# 1-Schematic_ISMWAVER433_MODULE.net
KiCad netlist of a schematic drawn in EasyEDA
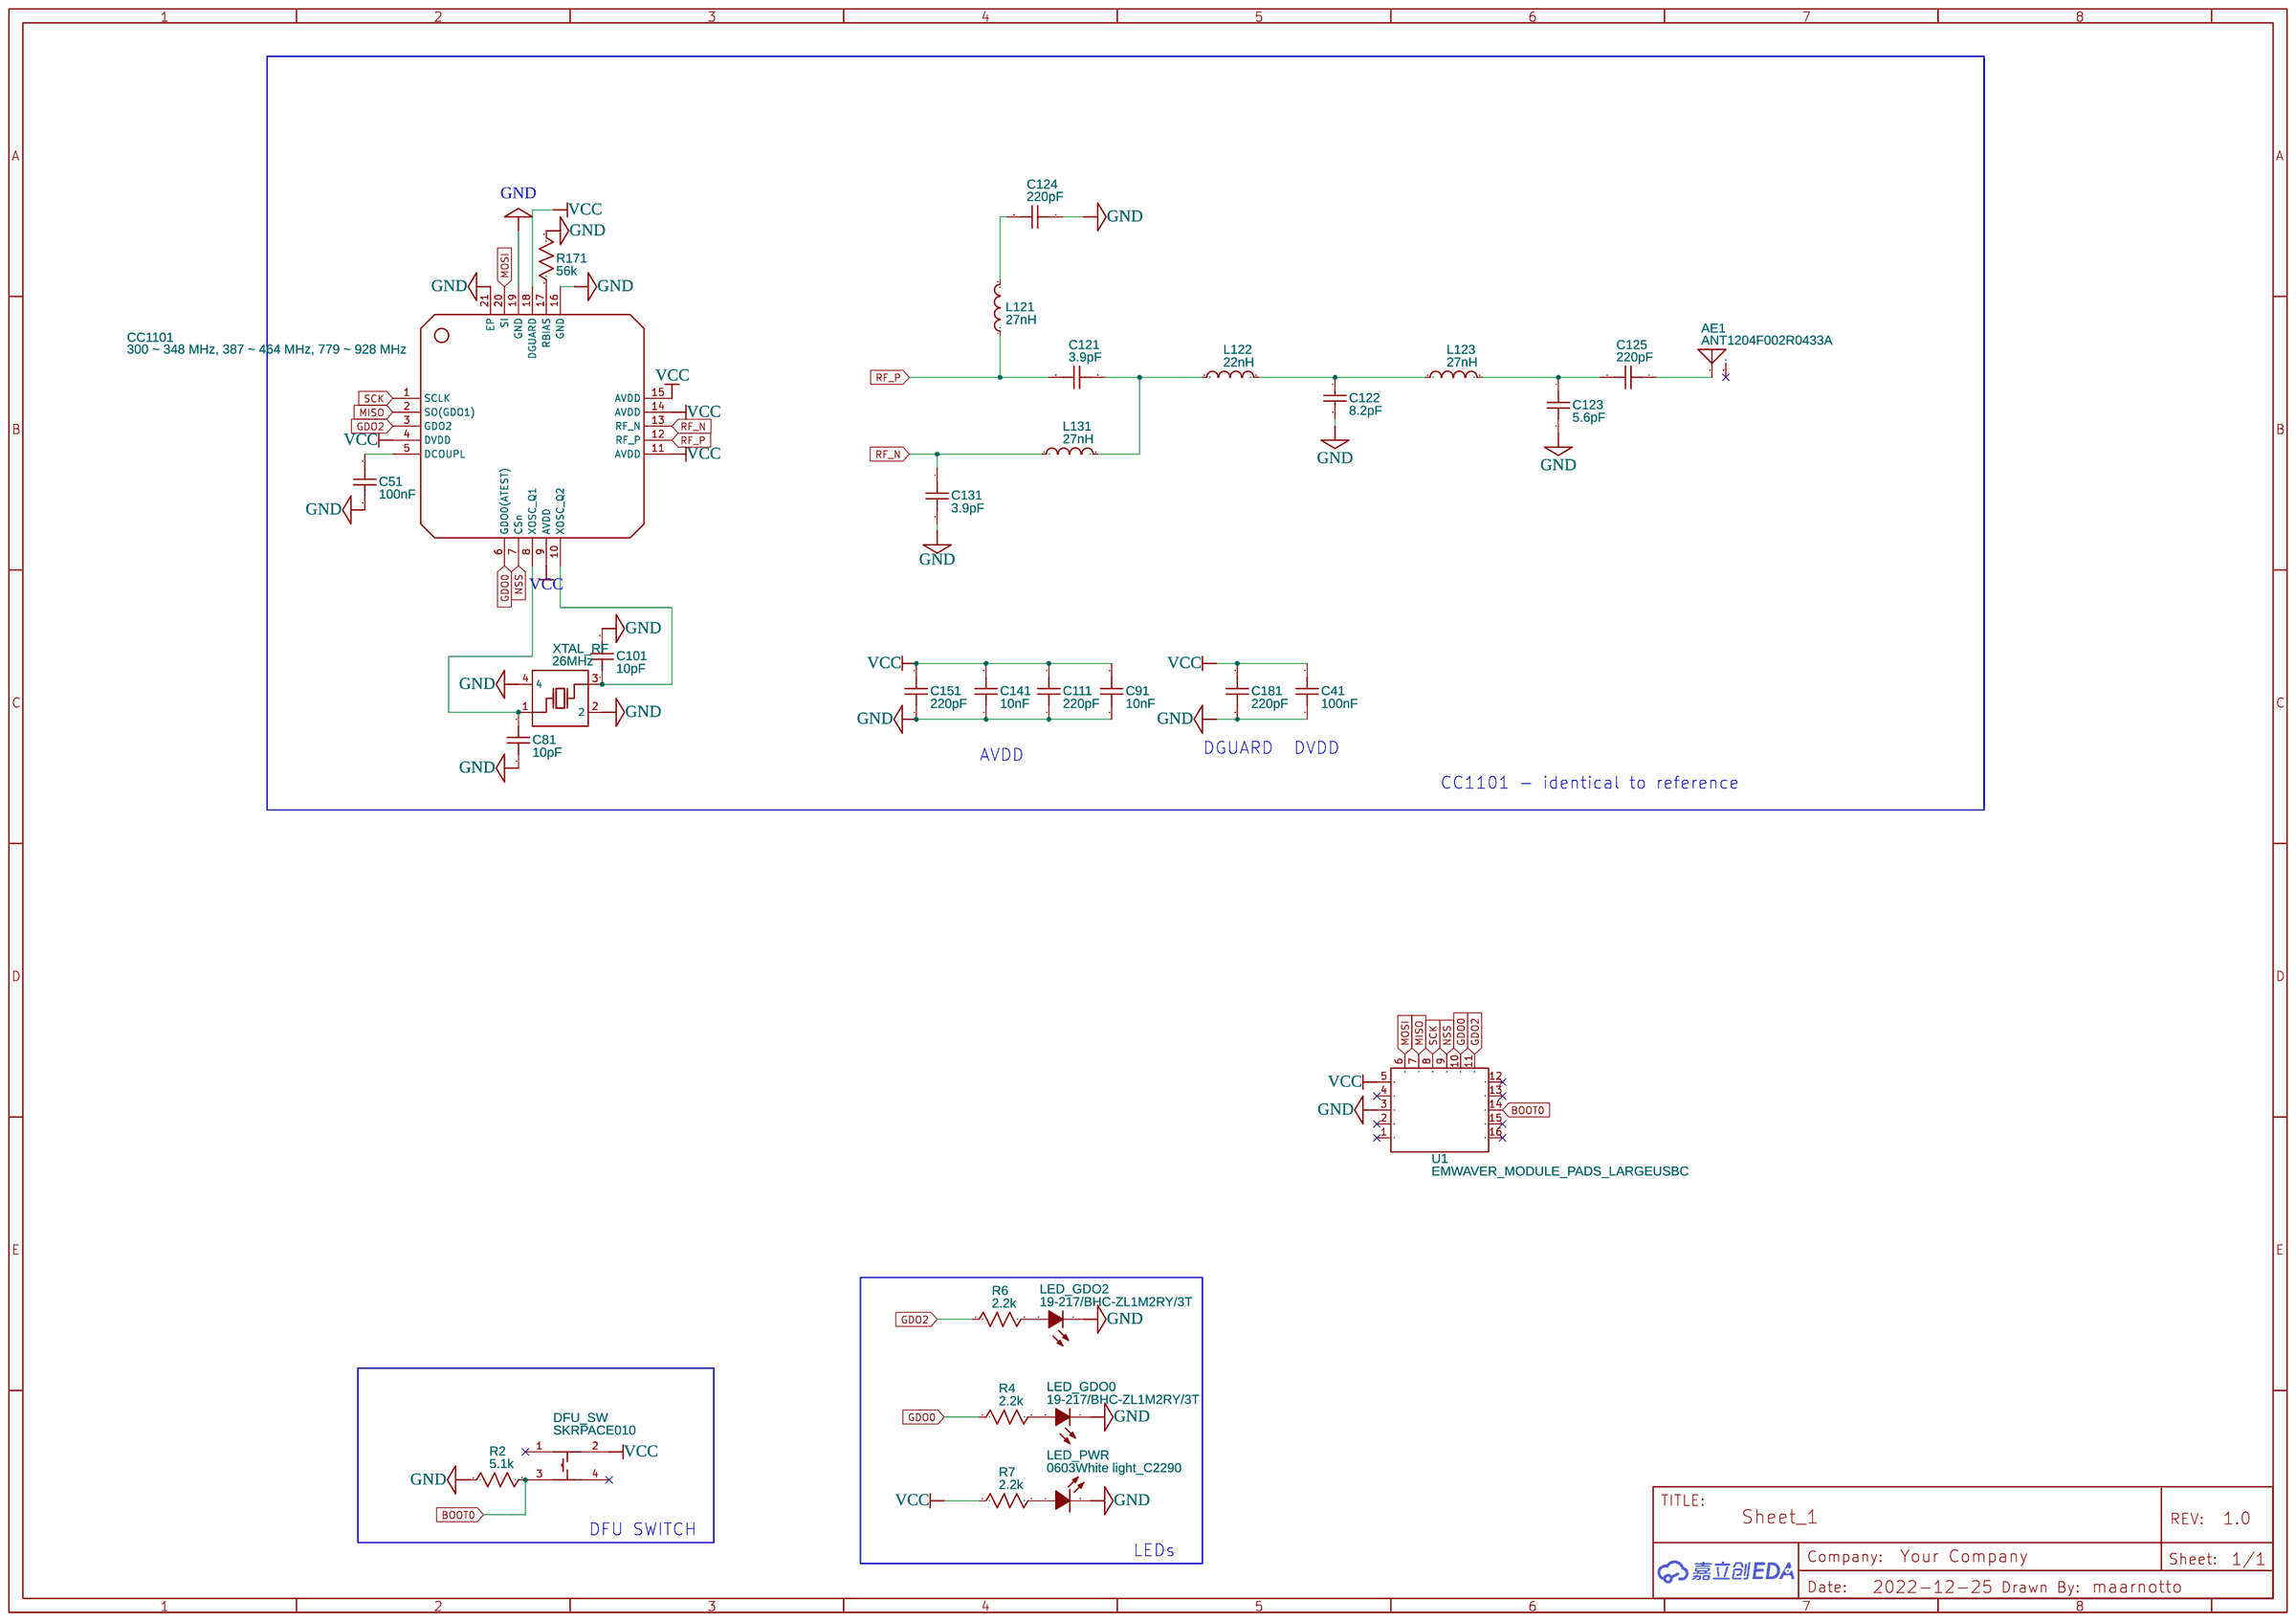
[diagram p0: schematic sheet]

(export (version "E")
  (design (tool "Eeschema 10.0.6"))
  (components
    (comp (ref "AE1")
      (value "ANT1204F002R0433A")
      (fields (field (name "Manufacturer") "YAGEO(国巨)"))
      (libsource (lib "") (part "ANT1204F002R0433A"))
    )
    (comp (ref "C41") (value "100nF") (libsource (lib "") (part "C_0402_US")))
    (comp (ref "C51") (value "100nF") (libsource (lib "") (part "C_0402_US")))
    (comp (ref "C81") (value "10pF") (libsource (lib "") (part "C_0402_US")))
    (comp (ref "C91") (value "10nF") (libsource (lib "") (part "C_0402_US")))
    (comp (ref "C101") (value "10pF") (libsource (lib "") (part "C_0402_US_2")))
    (comp (ref "C111") (value "220pF") (libsource (lib "") (part "C_0402_US")))
    (comp (ref "C121") (value "3.9pF") (libsource (lib "") (part "C_0402_US_1")))
    (comp (ref "C122")
      (value "8.2pF")
      (fields (field (name "Manufacturer Part") "0402CG8R2C500NT") (field (name "Manufacturer") "FH(风华)"))
      (libsource (lib "") (part "0402CG8R2C500NT"))
    )
    (comp (ref "C123") (value "5.6pF") (libsource (lib "") (part "C_0402_US")))
    (comp (ref "C124") (value "220pF") (libsource (lib "") (part "C_0402_US_1")))
    (comp (ref "C125") (value "220pF") (libsource (lib "") (part "C_0402_US_1")))
    (comp (ref "C131") (value "3.9pF") (libsource (lib "") (part "C_0402_US")))
    (comp (ref "C141") (value "10nF") (libsource (lib "") (part "C_0402_US")))
    (comp (ref "C151") (value "220pF") (libsource (lib "") (part "C_0402_US")))
    (comp (ref "C181") (value "220pF") (libsource (lib "") (part "C_0402_US")))
    (comp (ref "CC1101")
      (value "300 ~ 348 MHz, 387 ~ 464 MHz, 779 ~ 928 MHz")
      (fields (field (name "Manufacturer Part") "CC1101RGPR") (field (name "Manufacturer") "TI(德州仪器)"))
      (libsource (lib "") (part "CC1101RGPR"))
    )
    (comp (ref "DFU_SW")
      (value "SKRPACE010")
      (fields (field (name "Manufacturer") "ALPSALPINE(阿尔卑斯阿尔派)"))
      (libsource (lib "") (part "SKRPACE010"))
    )
    (comp (ref "L121") (value "27nH") (libsource (lib "") (part "L0402_US_1")))
    (comp (ref "L122") (value "22nH") (libsource (lib "") (part "L0402_US")))
    (comp (ref "L123") (value "27nH") (libsource (lib "") (part "L0402_US_2")))
    (comp (ref "L131") (value "27nH") (libsource (lib "") (part "L0402_US")))
    (comp (ref "LED_GDO0")
      (value "19-217/BHC-ZL1M2RY/3T")
      (fields (field (name "Manufacturer") "EVERLIGHT(亿光)"))
      (libsource (lib "") (part "19-217/BHC-ZL1M2RY/3T"))
    )
    (comp (ref "LED_GDO2")
      (value "19-217/BHC-ZL1M2RY/3T")
      (fields (field (name "Manufacturer") "EVERLIGHT(亿光)"))
      (libsource (lib "") (part "19-217/BHC-ZL1M2RY/3T"))
    )
    (comp (ref "LED_PWR")
      (value "0603White light_C2290")
      (fields (field (name "Manufacturer Part") "KT-0603白灯"))
      (libsource (lib "") (part "0603White light_C2290"))
    )
    (comp (ref "R2") (value "5.1k") (libsource (lib "") (part "R_0603_US")))
    (comp (ref "R4") (value "2.2k") (libsource (lib "") (part "R_0603_US")))
    (comp (ref "R6") (value "2.2k") (libsource (lib "") (part "R_0603_US")))
    (comp (ref "R7") (value "2.2k") (libsource (lib "") (part "R_0603_US")))
    (comp (ref "R171") (value "56k") (libsource (lib "") (part "R_0402_US")))
    (comp (ref "U1")
      (value "EMWAVER_MODULE_PADS_LARGEUSBC")
      (libsource (lib "") (part "EMWAVER_MODULE_PADS_LARGEUSBC"))
    )
    (comp (ref "XTAL_RF")
      (value "26MHz")
      (fields (field (name "Manufacturer Part") "3S26000333") (field (name "Manufacturer") "YL(惠伦晶体)"))
      (libsource (lib "") (part "3S26000333"))
    )
  )
  (nets
    (net (code "1") (name "BOOT0") (class "Default")
      (node (ref "DFU_SW") (pin "3") (pinfunction "3_3") (pintype "unspecified"))
      (node (ref "R2") (pin "2") (pinfunction "2_2") (pintype "unspecified"))
      (node (ref "U1") (pin "14") (pinfunction "14_14") (pintype "unspecified"))
    )
    (net (code "2") (name "GDO0") (class "Default")
      (node (ref "CC1101") (pin "6") (pinfunction "GDO0(ATEST)_6") (pintype "unspecified"))
      (node (ref "R4") (pin "1") (pinfunction "1_1") (pintype "unspecified"))
      (node (ref "U1") (pin "10") (pinfunction "10_10") (pintype "unspecified"))
    )
    (net (code "3") (name "GDO2") (class "Default")
      (node (ref "CC1101") (pin "3") (pinfunction "GDO2_3") (pintype "unspecified"))
      (node (ref "R6") (pin "1") (pinfunction "1_1") (pintype "unspecified"))
      (node (ref "U1") (pin "11") (pinfunction "11_11") (pintype "unspecified"))
    )
    (net (code "4") (name "GND") (class "Default")
      (node (ref "C101") (pin "2") (pinfunction "2_2") (pintype "unspecified"))
      (node (ref "C111") (pin "2") (pinfunction "2_2") (pintype "unspecified"))
      (node (ref "C122") (pin "1") (pinfunction "1_1") (pintype "input"))
      (node (ref "C123") (pin "2") (pinfunction "2_2") (pintype "unspecified"))
      (node (ref "C124") (pin "1") (pinfunction "1_1") (pintype "unspecified"))
      (node (ref "C131") (pin "2") (pinfunction "2_2") (pintype "unspecified"))
      (node (ref "C141") (pin "2") (pinfunction "2_2") (pintype "unspecified"))
      (node (ref "C151") (pin "2") (pinfunction "2_2") (pintype "unspecified"))
      (node (ref "C181") (pin "2") (pinfunction "2_2") (pintype "unspecified"))
      (node (ref "C41") (pin "2") (pinfunction "2_2") (pintype "unspecified"))
      (node (ref "C51") (pin "2") (pinfunction "2_2") (pintype "unspecified"))
      (node (ref "C81") (pin "2") (pinfunction "2_2") (pintype "unspecified"))
      (node (ref "C91") (pin "2") (pinfunction "2_2") (pintype "unspecified"))
      (node (ref "CC1101") (pin "16") (pinfunction "GND_16") (pintype "unspecified"))
      (node (ref "CC1101") (pin "19") (pinfunction "GND_19") (pintype "unspecified"))
      (node (ref "CC1101") (pin "21") (pinfunction "EP_21") (pintype "unspecified"))
      (node (ref "LED_GDO0") (pin "1") (pinfunction "C_1") (pintype "input"))
      (node (ref "LED_GDO2") (pin "1") (pinfunction "C_1") (pintype "input"))
      (node (ref "LED_PWR") (pin "2") (pinfunction "K_2") (pintype "unspecified"))
      (node (ref "R171") (pin "2") (pinfunction "2_2") (pintype "unspecified"))
      (node (ref "R2") (pin "1") (pinfunction "1_1") (pintype "unspecified"))
      (node (ref "U1") (pin "3") (pinfunction "3_3") (pintype "unspecified"))
      (node (ref "XTAL_RF") (pin "2") (pinfunction "2_2") (pintype "unspecified"))
      (node (ref "XTAL_RF") (pin "4") (pinfunction "4_4") (pintype "unspecified"))
    )
    (net (code "5") (name "MISO") (class "Default")
      (node (ref "CC1101") (pin "2") (pinfunction "SO(GDO1)_2") (pintype "unspecified"))
      (node (ref "U1") (pin "7") (pinfunction "7_7") (pintype "unspecified"))
    )
    (net (code "6") (name "MOSI") (class "Default")
      (node (ref "CC1101") (pin "20") (pinfunction "SI_20") (pintype "unspecified"))
      (node (ref "U1") (pin "6") (pinfunction "6_6") (pintype "unspecified"))
    )
    (net (code "7") (name "NSS") (class "Default")
      (node (ref "CC1101") (pin "7") (pinfunction "CSn_7") (pintype "unspecified"))
      (node (ref "U1") (pin "9") (pinfunction "9_9") (pintype "unspecified"))
    )
    (net (code "8") (name "Net-(AE1-PadS1)") (class "Default")
      (node (ref "AE1") (pin "S1") (pinfunction "S1_S1") (pintype "unspecified"))
      (node (ref "C125") (pin "1") (pinfunction "1_1") (pintype "unspecified"))
    )
    (net (code "9") (name "Net-(C121-Pad1)") (class "Default")
      (node (ref "C121") (pin "1") (pinfunction "1_1") (pintype "unspecified"))
      (node (ref "L122") (pin "1") (pinfunction "1_1") (pintype "unspecified"))
      (node (ref "L131") (pin "2") (pinfunction "2_2") (pintype "unspecified"))
    )
    (net (code "10") (name "Net-(C122-Pad2)") (class "Default")
      (node (ref "C122") (pin "2") (pinfunction "2_2") (pintype "input"))
      (node (ref "L122") (pin "2") (pinfunction "2_2") (pintype "unspecified"))
      (node (ref "L123") (pin "1") (pinfunction "1_1") (pintype "unspecified"))
    )
    (net (code "11") (name "Net-(C123-Pad1)") (class "Default")
      (node (ref "C123") (pin "1") (pinfunction "1_1") (pintype "unspecified"))
      (node (ref "C125") (pin "2") (pinfunction "2_2") (pintype "unspecified"))
      (node (ref "L123") (pin "2") (pinfunction "2_2") (pintype "unspecified"))
    )
    (net (code "12") (name "Net-(C124-Pad2)") (class "Default")
      (node (ref "C124") (pin "2") (pinfunction "2_2") (pintype "unspecified"))
      (node (ref "L121") (pin "2") (pinfunction "2_2") (pintype "unspecified"))
    )
    (net (code "13") (name "Net-(CC1101-DCOUPL)") (class "Default")
      (node (ref "C51") (pin "1") (pinfunction "1_1") (pintype "unspecified"))
      (node (ref "CC1101") (pin "5") (pinfunction "DCOUPL_5") (pintype "unspecified"))
    )
    (net (code "14") (name "Net-(CC1101-RBIAS)") (class "Default")
      (node (ref "CC1101") (pin "17") (pinfunction "RBIAS_17") (pintype "unspecified"))
      (node (ref "R171") (pin "1") (pinfunction "1_1") (pintype "unspecified"))
    )
    (net (code "15") (name "Net-(CC1101-XOSC_Q1)") (class "Default")
      (node (ref "C81") (pin "1") (pinfunction "1_1") (pintype "unspecified"))
      (node (ref "CC1101") (pin "8") (pinfunction "XOSC_Q1_8") (pintype "unspecified"))
      (node (ref "XTAL_RF") (pin "1") (pinfunction "OSC1_1") (pintype "unspecified"))
    )
    (net (code "16") (name "Net-(CC1101-XOSC_Q2)") (class "Default")
      (node (ref "C101") (pin "1") (pinfunction "1_1") (pintype "unspecified"))
      (node (ref "CC1101") (pin "10") (pinfunction "XOSC_Q2_10") (pintype "unspecified"))
      (node (ref "XTAL_RF") (pin "3") (pinfunction "OSC2_3") (pintype "unspecified"))
    )
    (net (code "17") (name "Net-(LED_GDO0-A)") (class "Default")
      (node (ref "LED_GDO0") (pin "2") (pinfunction "A_2") (pintype "input"))
      (node (ref "R4") (pin "2") (pinfunction "2_2") (pintype "unspecified"))
    )
    (net (code "18") (name "Net-(LED_GDO2-A)") (class "Default")
      (node (ref "LED_GDO2") (pin "2") (pinfunction "A_2") (pintype "input"))
      (node (ref "R6") (pin "2") (pinfunction "2_2") (pintype "unspecified"))
    )
    (net (code "19") (name "Net-(LED_PWR-A)") (class "Default")
      (node (ref "LED_PWR") (pin "1") (pinfunction "A_1") (pintype "unspecified"))
      (node (ref "R7") (pin "2") (pinfunction "2_2") (pintype "unspecified"))
    )
    (net (code "20") (name "RF_N") (class "Default")
      (node (ref "C131") (pin "1") (pinfunction "1_1") (pintype "unspecified"))
      (node (ref "CC1101") (pin "13") (pinfunction "RF_N_13") (pintype "unspecified"))
      (node (ref "L131") (pin "1") (pinfunction "1_1") (pintype "unspecified"))
    )
    (net (code "21") (name "RF_P") (class "Default")
      (node (ref "C121") (pin "2") (pinfunction "2_2") (pintype "unspecified"))
      (node (ref "CC1101") (pin "12") (pinfunction "RF_P_12") (pintype "unspecified"))
      (node (ref "L121") (pin "1") (pinfunction "1_1") (pintype "unspecified"))
    )
    (net (code "22") (name "SCK") (class "Default")
      (node (ref "CC1101") (pin "1") (pinfunction "SCLK_1") (pintype "unspecified"))
      (node (ref "U1") (pin "8") (pinfunction "8_8") (pintype "unspecified"))
    )
    (net (code "23") (name "VCC") (class "Default")
      (node (ref "C111") (pin "1") (pinfunction "1_1") (pintype "unspecified"))
      (node (ref "C141") (pin "1") (pinfunction "1_1") (pintype "unspecified"))
      (node (ref "C151") (pin "1") (pinfunction "1_1") (pintype "unspecified"))
      (node (ref "C181") (pin "1") (pinfunction "1_1") (pintype "unspecified"))
      (node (ref "C41") (pin "1") (pinfunction "1_1") (pintype "unspecified"))
      (node (ref "C91") (pin "1") (pinfunction "1_1") (pintype "unspecified"))
      (node (ref "CC1101") (pin "11") (pinfunction "AVDD_11") (pintype "unspecified"))
      (node (ref "CC1101") (pin "14") (pinfunction "AVDD_14") (pintype "unspecified"))
      (node (ref "CC1101") (pin "15") (pinfunction "AVDD_15") (pintype "unspecified"))
      (node (ref "CC1101") (pin "18") (pinfunction "DGUARD_18") (pintype "unspecified"))
      (node (ref "CC1101") (pin "4") (pinfunction "DVDD_4") (pintype "unspecified"))
      (node (ref "CC1101") (pin "9") (pinfunction "AVDD_9") (pintype "unspecified"))
      (node (ref "DFU_SW") (pin "2") (pinfunction "2_2") (pintype "unspecified"))
      (node (ref "R7") (pin "1") (pinfunction "1_1") (pintype "unspecified"))
      (node (ref "U1") (pin "5") (pinfunction "5_5") (pintype "unspecified"))
    )
    (net (code "24") (name "unconnected-(AE1-PadS2)") (class "Default")
      (node (ref "AE1") (pin "S2") (pinfunction "S2_S2") (pintype "unspecified+no_connect"))
    )
    (net (code "25") (name "unconnected-(DFU_SW-Pad1)") (class "Default")
      (node (ref "DFU_SW") (pin "1") (pinfunction "1_1") (pintype "unspecified+no_connect"))
    )
    (net (code "26") (name "unconnected-(DFU_SW-Pad4)") (class "Default")
      (node (ref "DFU_SW") (pin "4") (pinfunction "4_4") (pintype "unspecified+no_connect"))
    )
    (net (code "27") (name "unconnected-(U1-Pad1)") (class "Default")
      (node (ref "U1") (pin "1") (pinfunction "1_1") (pintype "unspecified+no_connect"))
    )
    (net (code "28") (name "unconnected-(U1-Pad2)") (class "Default")
      (node (ref "U1") (pin "2") (pinfunction "2_2") (pintype "unspecified+no_connect"))
    )
    (net (code "29") (name "unconnected-(U1-Pad4)") (class "Default")
      (node (ref "U1") (pin "4") (pinfunction "4_4") (pintype "unspecified+no_connect"))
    )
    (net (code "30") (name "unconnected-(U1-Pad12)") (class "Default")
      (node (ref "U1") (pin "12") (pinfunction "12_12") (pintype "unspecified+no_connect"))
    )
    (net (code "31") (name "unconnected-(U1-Pad13)") (class "Default")
      (node (ref "U1") (pin "13") (pinfunction "13_13") (pintype "unspecified+no_connect"))
    )
    (net (code "32") (name "unconnected-(U1-Pad15)") (class "Default")
      (node (ref "U1") (pin "15") (pinfunction "15_15") (pintype "unspecified+no_connect"))
    )
    (net (code "33") (name "unconnected-(U1-Pad16)") (class "Default")
      (node (ref "U1") (pin "16") (pinfunction "16_16") (pintype "unspecified+no_connect"))
    )
  )
)
